# RGBLEDv1.net
KiCad netlist of a schematic drawn in EAGLE
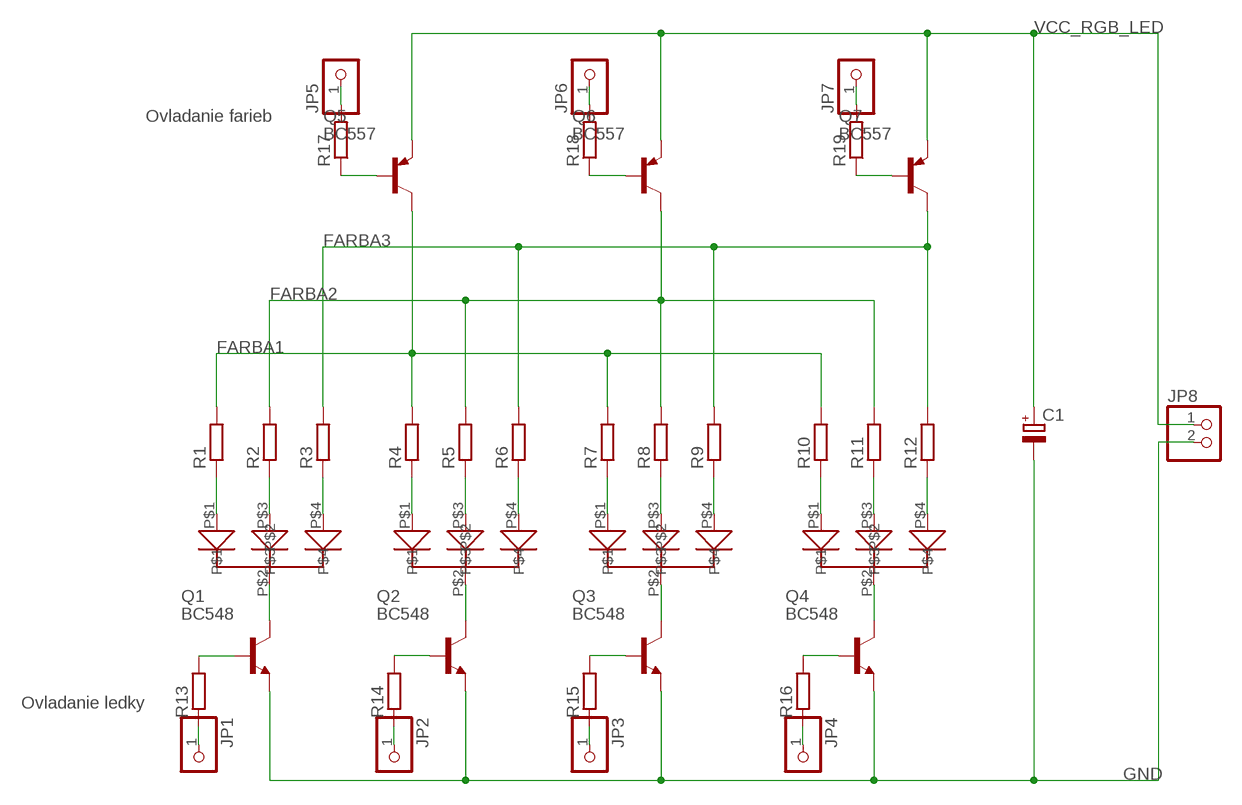
[diagram p0: schematic, sheet 1]

(export (version "E")
  (design (tool "Eeschema 10.0.6"))
  (components
    (comp (ref "C1")
      (value "CPOL-EUE2.5-7")
      (footprint "eagle-import:E2,5-7")
      (libsource (lib "eagle-import") (part "CPOL-EUE2.5-7"))
    )
    (comp (ref "JP1")
      (value "PINHD-1X1")
      (footprint "eagle-import:1X01")
      (libsource (lib "eagle-import") (part "PINHD-1X1"))
    )
    (comp (ref "JP2")
      (value "PINHD-1X1")
      (footprint "eagle-import:1X01")
      (libsource (lib "eagle-import") (part "PINHD-1X1"))
    )
    (comp (ref "JP3")
      (value "PINHD-1X1")
      (footprint "eagle-import:1X01")
      (libsource (lib "eagle-import") (part "PINHD-1X1"))
    )
    (comp (ref "JP4")
      (value "PINHD-1X1")
      (footprint "eagle-import:1X01")
      (libsource (lib "eagle-import") (part "PINHD-1X1"))
    )
    (comp (ref "JP5")
      (value "PINHD-1X1")
      (footprint "eagle-import:1X01")
      (libsource (lib "eagle-import") (part "PINHD-1X1"))
    )
    (comp (ref "JP6")
      (value "PINHD-1X1")
      (footprint "eagle-import:1X01")
      (libsource (lib "eagle-import") (part "PINHD-1X1"))
    )
    (comp (ref "JP7")
      (value "PINHD-1X1")
      (footprint "eagle-import:1X01")
      (libsource (lib "eagle-import") (part "PINHD-1X1"))
    )
    (comp (ref "JP8")
      (value "PINHD-1X2")
      (footprint "eagle-import:1X02")
      (libsource (lib "eagle-import") (part "PINHD-1X2"))
    )
    (comp (ref "Q1")
      (value "BC548")
      (footprint "eagle-import:TO92-EBC")
      (libsource (lib "eagle-import") (part "BC548"))
    )
    (comp (ref "Q2")
      (value "BC548")
      (footprint "eagle-import:TO92-EBC")
      (libsource (lib "eagle-import") (part "BC548"))
    )
    (comp (ref "Q3")
      (value "BC548")
      (footprint "eagle-import:TO92-EBC")
      (libsource (lib "eagle-import") (part "BC548"))
    )
    (comp (ref "Q4")
      (value "BC548")
      (footprint "eagle-import:TO92-EBC")
      (libsource (lib "eagle-import") (part "BC548"))
    )
    (comp (ref "Q5")
      (value "BC557")
      (footprint "eagle-import:TO92")
      (libsource (lib "eagle-import") (part "BC557"))
    )
    (comp (ref "Q6")
      (value "BC557")
      (footprint "eagle-import:TO92")
      (libsource (lib "eagle-import") (part "BC557"))
    )
    (comp (ref "Q7")
      (value "BC557")
      (footprint "eagle-import:TO92")
      (libsource (lib "eagle-import") (part "BC557"))
    )
    (comp (ref "R1")
      (value "R-EU_0207/10")
      (footprint "eagle-import:0207_10")
      (libsource (lib "eagle-import") (part "R-EU_0207/10"))
    )
    (comp (ref "R2")
      (value "R-EU_0207/10")
      (footprint "eagle-import:0207_10")
      (libsource (lib "eagle-import") (part "R-EU_0207/10"))
    )
    (comp (ref "R3")
      (value "R-EU_0207/10")
      (footprint "eagle-import:0207_10")
      (libsource (lib "eagle-import") (part "R-EU_0207/10"))
    )
    (comp (ref "R4")
      (value "R-EU_0207/10")
      (footprint "eagle-import:0207_10")
      (libsource (lib "eagle-import") (part "R-EU_0207/10"))
    )
    (comp (ref "R5")
      (value "R-EU_0207/10")
      (footprint "eagle-import:0207_10")
      (libsource (lib "eagle-import") (part "R-EU_0207/10"))
    )
    (comp (ref "R6")
      (value "R-EU_0207/10")
      (footprint "eagle-import:0207_10")
      (libsource (lib "eagle-import") (part "R-EU_0207/10"))
    )
    (comp (ref "R7")
      (value "R-EU_0207/10")
      (footprint "eagle-import:0207_10")
      (libsource (lib "eagle-import") (part "R-EU_0207/10"))
    )
    (comp (ref "R8")
      (value "R-EU_0207/10")
      (footprint "eagle-import:0207_10")
      (libsource (lib "eagle-import") (part "R-EU_0207/10"))
    )
    (comp (ref "R9")
      (value "R-EU_0207/10")
      (footprint "eagle-import:0207_10")
      (libsource (lib "eagle-import") (part "R-EU_0207/10"))
    )
    (comp (ref "R10")
      (value "R-EU_0207/10")
      (footprint "eagle-import:0207_10")
      (libsource (lib "eagle-import") (part "R-EU_0207/10"))
    )
    (comp (ref "R11")
      (value "R-EU_0207/10")
      (footprint "eagle-import:0207_10")
      (libsource (lib "eagle-import") (part "R-EU_0207/10"))
    )
    (comp (ref "R12")
      (value "R-EU_0207/10")
      (footprint "eagle-import:0207_10")
      (libsource (lib "eagle-import") (part "R-EU_0207/10"))
    )
    (comp (ref "R13")
      (value "R-EU_0207/10")
      (footprint "eagle-import:0207_10")
      (libsource (lib "eagle-import") (part "R-EU_0207/10"))
    )
    (comp (ref "R14")
      (value "R-EU_0207/10")
      (footprint "eagle-import:0207_10")
      (libsource (lib "eagle-import") (part "R-EU_0207/10"))
    )
    (comp (ref "R15")
      (value "R-EU_0207/10")
      (footprint "eagle-import:0207_10")
      (libsource (lib "eagle-import") (part "R-EU_0207/10"))
    )
    (comp (ref "R16")
      (value "R-EU_0207/10")
      (footprint "eagle-import:0207_10")
      (libsource (lib "eagle-import") (part "R-EU_0207/10"))
    )
    (comp (ref "R17")
      (value "R-EU_0207/10")
      (footprint "eagle-import:0207_10")
      (libsource (lib "eagle-import") (part "R-EU_0207/10"))
    )
    (comp (ref "R18")
      (value "R-EU_0207/10")
      (footprint "eagle-import:0207_10")
      (libsource (lib "eagle-import") (part "R-EU_0207/10"))
    )
    (comp (ref "R19")
      (value "R-EU_0207/10")
      (footprint "eagle-import:0207_10")
      (libsource (lib "eagle-import") (part "R-EU_0207/10"))
    )
    (comp (ref "RGBLED1")
      (value "RGBLED")
      (footprint "eagle-import:RGBLED")
      (libsource (lib "eagle-import") (part "RGBLED"))
    )
    (comp (ref "RGBLED2")
      (value "RGBLED")
      (footprint "eagle-import:RGBLED")
      (libsource (lib "eagle-import") (part "RGBLED"))
    )
    (comp (ref "RGBLED3")
      (value "RGBLED")
      (footprint "eagle-import:RGBLED")
      (libsource (lib "eagle-import") (part "RGBLED"))
    )
    (comp (ref "RGBLED4")
      (value "RGBLED")
      (footprint "eagle-import:RGBLED")
      (libsource (lib "eagle-import") (part "RGBLED"))
    )
  )
  (nets
    (net (code "1") (name "/FARBA1") (class "Default")
      (node (ref "Q5") (pin "3") (pinfunction "C_3") (pintype "passive"))
      (node (ref "R1") (pin "2") (pinfunction "2_2") (pintype "passive"))
      (node (ref "R10") (pin "2") (pinfunction "2_2") (pintype "passive"))
      (node (ref "R4") (pin "2") (pinfunction "2_2") (pintype "passive"))
      (node (ref "R7") (pin "2") (pinfunction "2_2") (pintype "passive"))
    )
    (net (code "2") (name "/FARBA2") (class "Default")
      (node (ref "Q6") (pin "3") (pinfunction "C_3") (pintype "passive"))
      (node (ref "R11") (pin "2") (pinfunction "2_2") (pintype "passive"))
      (node (ref "R2") (pin "2") (pinfunction "2_2") (pintype "passive"))
      (node (ref "R5") (pin "2") (pinfunction "2_2") (pintype "passive"))
      (node (ref "R8") (pin "2") (pinfunction "2_2") (pintype "passive"))
    )
    (net (code "3") (name "/FARBA3") (class "Default")
      (node (ref "Q7") (pin "3") (pinfunction "C_3") (pintype "passive"))
      (node (ref "R12") (pin "2") (pinfunction "2_2") (pintype "passive"))
      (node (ref "R3") (pin "2") (pinfunction "2_2") (pintype "passive"))
      (node (ref "R6") (pin "2") (pinfunction "2_2") (pintype "passive"))
      (node (ref "R9") (pin "2") (pinfunction "2_2") (pintype "passive"))
    )
    (net (code "4") (name "/GND") (class "Default")
      (node (ref "C1") (pin "-") (pinfunction "-_-") (pintype "passive"))
      (node (ref "JP8") (pin "2") (pinfunction "2_2") (pintype "passive"))
      (node (ref "Q1") (pin "E") (pinfunction "E_E") (pintype "passive"))
      (node (ref "Q2") (pin "E") (pinfunction "E_E") (pintype "passive"))
      (node (ref "Q3") (pin "E") (pinfunction "E_E") (pintype "passive"))
      (node (ref "Q4") (pin "E") (pinfunction "E_E") (pintype "passive"))
    )
    (net (code "5") (name "/VCC_RGB_LED") (class "Default")
      (node (ref "C1") (pin "+") (pinfunction "+_+") (pintype "passive"))
      (node (ref "JP8") (pin "1") (pinfunction "1_1") (pintype "passive"))
      (node (ref "Q5") (pin "1") (pinfunction "E_1") (pintype "passive"))
      (node (ref "Q6") (pin "1") (pinfunction "E_1") (pintype "passive"))
      (node (ref "Q7") (pin "1") (pinfunction "E_1") (pintype "passive"))
    )
    (net (code "6") (name "Net-(JP1-Pad1)") (class "Default")
      (node (ref "JP1") (pin "1") (pinfunction "1_1") (pintype "passive"))
      (node (ref "R13") (pin "1") (pinfunction "1_1") (pintype "passive"))
    )
    (net (code "7") (name "Net-(JP2-Pad1)") (class "Default")
      (node (ref "JP2") (pin "1") (pinfunction "1_1") (pintype "passive"))
      (node (ref "R14") (pin "1") (pinfunction "1_1") (pintype "passive"))
    )
    (net (code "8") (name "Net-(JP3-Pad1)") (class "Default")
      (node (ref "JP3") (pin "1") (pinfunction "1_1") (pintype "passive"))
      (node (ref "R15") (pin "1") (pinfunction "1_1") (pintype "passive"))
    )
    (net (code "9") (name "Net-(JP4-Pad1)") (class "Default")
      (node (ref "JP4") (pin "1") (pinfunction "1_1") (pintype "passive"))
      (node (ref "R16") (pin "1") (pinfunction "1_1") (pintype "passive"))
    )
    (net (code "10") (name "Net-(JP5-Pad1)") (class "Default")
      (node (ref "JP5") (pin "1") (pinfunction "1_1") (pintype "passive"))
      (node (ref "R17") (pin "2") (pinfunction "2_2") (pintype "passive"))
    )
    (net (code "11") (name "Net-(JP6-Pad1)") (class "Default")
      (node (ref "JP6") (pin "1") (pinfunction "1_1") (pintype "passive"))
      (node (ref "R18") (pin "2") (pinfunction "2_2") (pintype "passive"))
    )
    (net (code "12") (name "Net-(JP7-Pad1)") (class "Default")
      (node (ref "JP7") (pin "1") (pinfunction "1_1") (pintype "passive"))
      (node (ref "R19") (pin "2") (pinfunction "2_2") (pintype "passive"))
    )
    (net (code "13") (name "Net-(Q1-PadB)") (class "Default")
      (node (ref "Q1") (pin "B") (pinfunction "B_B") (pintype "passive"))
      (node (ref "R13") (pin "2") (pinfunction "2_2") (pintype "passive"))
    )
    (net (code "14") (name "Net-(Q1-PadC)") (class "Default")
      (node (ref "Q1") (pin "C") (pinfunction "C_C") (pintype "passive"))
      (node (ref "RGBLED1") (pin "P$2") (pinfunction "P$2_P$2") (pintype "output"))
    )
    (net (code "15") (name "Net-(Q2-PadB)") (class "Default")
      (node (ref "Q2") (pin "B") (pinfunction "B_B") (pintype "passive"))
      (node (ref "R14") (pin "2") (pinfunction "2_2") (pintype "passive"))
    )
    (net (code "16") (name "Net-(Q2-PadC)") (class "Default")
      (node (ref "Q2") (pin "C") (pinfunction "C_C") (pintype "passive"))
      (node (ref "RGBLED2") (pin "P$2") (pinfunction "P$2_P$2") (pintype "output"))
    )
    (net (code "17") (name "Net-(Q3-PadB)") (class "Default")
      (node (ref "Q3") (pin "B") (pinfunction "B_B") (pintype "passive"))
      (node (ref "R15") (pin "2") (pinfunction "2_2") (pintype "passive"))
    )
    (net (code "18") (name "Net-(Q3-PadC)") (class "Default")
      (node (ref "Q3") (pin "C") (pinfunction "C_C") (pintype "passive"))
      (node (ref "RGBLED3") (pin "P$2") (pinfunction "P$2_P$2") (pintype "output"))
    )
    (net (code "19") (name "Net-(Q4-PadB)") (class "Default")
      (node (ref "Q4") (pin "B") (pinfunction "B_B") (pintype "passive"))
      (node (ref "R16") (pin "2") (pinfunction "2_2") (pintype "passive"))
    )
    (net (code "20") (name "Net-(Q4-PadC)") (class "Default")
      (node (ref "Q4") (pin "C") (pinfunction "C_C") (pintype "passive"))
      (node (ref "RGBLED4") (pin "P$2") (pinfunction "P$2_P$2") (pintype "output"))
    )
    (net (code "21") (name "Net-(Q5-B)") (class "Default")
      (node (ref "Q5") (pin "2") (pinfunction "B_2") (pintype "passive"))
      (node (ref "R17") (pin "1") (pinfunction "1_1") (pintype "passive"))
    )
    (net (code "22") (name "Net-(Q6-B)") (class "Default")
      (node (ref "Q6") (pin "2") (pinfunction "B_2") (pintype "passive"))
      (node (ref "R18") (pin "1") (pinfunction "1_1") (pintype "passive"))
    )
    (net (code "23") (name "Net-(Q7-B)") (class "Default")
      (node (ref "Q7") (pin "2") (pinfunction "B_2") (pintype "passive"))
      (node (ref "R19") (pin "1") (pinfunction "1_1") (pintype "passive"))
    )
    (net (code "24") (name "Net-(R1-Pad1)") (class "Default")
      (node (ref "R1") (pin "1") (pinfunction "1_1") (pintype "passive"))
      (node (ref "RGBLED1") (pin "P$1") (pinfunction "P$1_P$1") (pintype "input"))
    )
    (net (code "25") (name "Net-(R2-Pad1)") (class "Default")
      (node (ref "R2") (pin "1") (pinfunction "1_1") (pintype "passive"))
      (node (ref "RGBLED1") (pin "P$3") (pinfunction "P$3_P$3") (pintype "input"))
    )
    (net (code "26") (name "Net-(R3-Pad1)") (class "Default")
      (node (ref "R3") (pin "1") (pinfunction "1_1") (pintype "passive"))
      (node (ref "RGBLED1") (pin "P$4") (pinfunction "P$4_P$4") (pintype "input"))
    )
    (net (code "27") (name "Net-(R4-Pad1)") (class "Default")
      (node (ref "R4") (pin "1") (pinfunction "1_1") (pintype "passive"))
      (node (ref "RGBLED2") (pin "P$1") (pinfunction "P$1_P$1") (pintype "input"))
    )
    (net (code "28") (name "Net-(R5-Pad1)") (class "Default")
      (node (ref "R5") (pin "1") (pinfunction "1_1") (pintype "passive"))
      (node (ref "RGBLED2") (pin "P$3") (pinfunction "P$3_P$3") (pintype "input"))
    )
    (net (code "29") (name "Net-(R6-Pad1)") (class "Default")
      (node (ref "R6") (pin "1") (pinfunction "1_1") (pintype "passive"))
      (node (ref "RGBLED2") (pin "P$4") (pinfunction "P$4_P$4") (pintype "input"))
    )
    (net (code "30") (name "Net-(R7-Pad1)") (class "Default")
      (node (ref "R7") (pin "1") (pinfunction "1_1") (pintype "passive"))
      (node (ref "RGBLED3") (pin "P$1") (pinfunction "P$1_P$1") (pintype "input"))
    )
    (net (code "31") (name "Net-(R8-Pad1)") (class "Default")
      (node (ref "R8") (pin "1") (pinfunction "1_1") (pintype "passive"))
      (node (ref "RGBLED3") (pin "P$3") (pinfunction "P$3_P$3") (pintype "input"))
    )
    (net (code "32") (name "Net-(R9-Pad1)") (class "Default")
      (node (ref "R9") (pin "1") (pinfunction "1_1") (pintype "passive"))
      (node (ref "RGBLED3") (pin "P$4") (pinfunction "P$4_P$4") (pintype "input"))
    )
    (net (code "33") (name "Net-(R10-Pad1)") (class "Default")
      (node (ref "R10") (pin "1") (pinfunction "1_1") (pintype "passive"))
      (node (ref "RGBLED4") (pin "P$1") (pinfunction "P$1_P$1") (pintype "input"))
    )
    (net (code "34") (name "Net-(R11-Pad1)") (class "Default")
      (node (ref "R11") (pin "1") (pinfunction "1_1") (pintype "passive"))
      (node (ref "RGBLED4") (pin "P$3") (pinfunction "P$3_P$3") (pintype "input"))
    )
    (net (code "35") (name "Net-(R12-Pad1)") (class "Default")
      (node (ref "R12") (pin "1") (pinfunction "1_1") (pintype "passive"))
      (node (ref "RGBLED4") (pin "P$4") (pinfunction "P$4_P$4") (pintype "input"))
    )
  )
)
